# Bomba.net
KiCad netlist of a schematic drawn in EAGLE
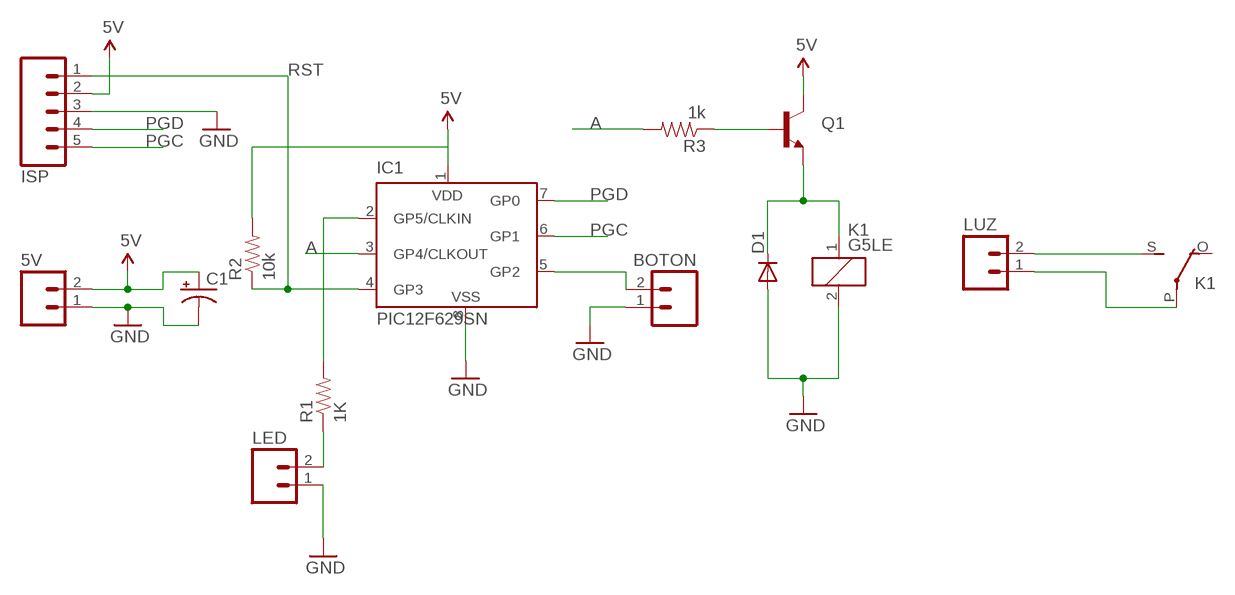
[diagram p0: schematic, sheet 1]

(export (version "E")
  (design (tool "Eeschema 10.0.6"))
  (components
    (comp (ref "5V")
      (value "M025MM")
      (footprint "eagle-import:SCREWTERMINAL-5MM-2")
      (libsource (lib "eagle-import") (part "M025MM"))
    )
    (comp (ref "BOTON")
      (value "M025MM")
      (footprint "eagle-import:SCREWTERMINAL-5MM-2")
      (libsource (lib "eagle-import") (part "M025MM"))
    )
    (comp (ref "C1")
      (value "CAP_POLPTH1")
      (footprint "eagle-import:CPOL-RADIAL-100UF-25V")
      (libsource (lib "eagle-import") (part "CAP_POLPTH1"))
    )
    (comp (ref "D1")
      (value "DIODE1N4148")
      (footprint "eagle-import:DIODE-1N4148")
      (libsource (lib "eagle-import") (part "DIODE1N4148"))
    )
    (comp (ref "IC1")
      (value "PIC12F629SN")
      (footprint "eagle-import:SO-08")
      (fields (field (name "MF") "MICROCHIP") (field (name "MPN") "PIC12F629-I/SN"))
      (libsource (lib "eagle-import") (part "PIC12F6SN29"))
    )
    (comp (ref "ISP")
      (value "M05LOCK_LONGPADS")
      (footprint "eagle-import:1X05_LOCK_LONGPADS")
      (libsource (lib "eagle-import") (part "M05LOCK_LONGPADS"))
    )
    (comp (ref "K1")
      (value "G5LE")
      (footprint "eagle-import:G5LE")
      (libsource (lib "eagle-import") (part "G5LE"))
    )
    (comp (ref "LED")
      (value "M02LOCK_LONGPADS")
      (footprint "eagle-import:1X02_LOCK_LONGPADS")
      (libsource (lib "eagle-import") (part "M02LOCK_LONGPADS"))
    )
    (comp (ref "LUZ")
      (value "M025MM")
      (footprint "eagle-import:SCREWTERMINAL-5MM-2")
      (libsource (lib "eagle-import") (part "M025MM"))
    )
    (comp (ref "Q1")
      (value "TRANSISTOR_NPNSOT23")
      (footprint "eagle-import:SOT23")
      (libsource (lib "eagle-import") (part "TRANSISTOR_NPNSOT23"))
    )
    (comp (ref "R1")
      (value "1K")
      (footprint "eagle-import:1206")
      (libsource (lib "eagle-import") (part "RESISTOR1206"))
    )
    (comp (ref "R2")
      (value "10k")
      (footprint "eagle-import:1206")
      (libsource (lib "eagle-import") (part "RESISTOR1206"))
    )
    (comp (ref "R3")
      (value "1k")
      (footprint "eagle-import:1206")
      (libsource (lib "eagle-import") (part "RESISTOR1206"))
    )
  )
  (nets
    (net (code "1") (name "/A") (class "Default")
      (node (ref "IC1") (pin "3") (pinfunction "GP4/CLKOUT_3") (pintype "bidirectional"))
      (node (ref "R3") (pin "2") (pinfunction "2_2") (pintype "passive"))
    )
    (net (code "2") (name "/PGC") (class "Default")
      (node (ref "IC1") (pin "6") (pinfunction "GP1_6") (pintype "bidirectional"))
      (node (ref "ISP") (pin "5") (pinfunction "5_5") (pintype "passive"))
    )
    (net (code "3") (name "/PGD") (class "Default")
      (node (ref "IC1") (pin "7") (pinfunction "GP0_7") (pintype "bidirectional"))
      (node (ref "ISP") (pin "4") (pinfunction "4_4") (pintype "passive"))
    )
    (net (code "4") (name "/RST") (class "Default")
      (node (ref "IC1") (pin "4") (pinfunction "GP3_4") (pintype "input"))
      (node (ref "ISP") (pin "1") (pinfunction "1_1") (pintype "passive"))
      (node (ref "R2") (pin "1") (pinfunction "1_1") (pintype "passive"))
    )
    (net (code "5") (name "5V") (class "Default")
      (node (ref "5V") (pin "2") (pinfunction "2_2") (pintype "passive"))
      (node (ref "C1") (pin "1") (pinfunction "+_1") (pintype "passive"))
      (node (ref "IC1") (pin "1") (pinfunction "VDD_1") (pintype "power_in"))
      (node (ref "ISP") (pin "2") (pinfunction "2_2") (pintype "passive"))
      (node (ref "Q1") (pin "3") (pinfunction "C_3") (pintype "passive"))
      (node (ref "R2") (pin "2") (pinfunction "2_2") (pintype "passive"))
    )
    (net (code "6") (name "GND") (class "Default")
      (node (ref "5V") (pin "1") (pinfunction "1_1") (pintype "passive"))
      (node (ref "BOTON") (pin "1") (pinfunction "1_1") (pintype "passive"))
      (node (ref "C1") (pin "2") (pinfunction "-_2") (pintype "passive"))
      (node (ref "D1") (pin "A") (pinfunction "A_A") (pintype "passive"))
      (node (ref "IC1") (pin "8") (pinfunction "VSS_8") (pintype "power_in"))
      (node (ref "ISP") (pin "3") (pinfunction "3_3") (pintype "passive"))
      (node (ref "K1") (pin "2") (pinfunction "2_2") (pintype "passive"))
      (node (ref "LED") (pin "1") (pinfunction "1_1") (pintype "passive"))
    )
    (net (code "7") (name "Net-(IC1-GP2)") (class "Default")
      (node (ref "BOTON") (pin "2") (pinfunction "2_2") (pintype "passive"))
      (node (ref "IC1") (pin "5") (pinfunction "GP2_5") (pintype "bidirectional"))
    )
    (net (code "8") (name "Net-(IC1-GP5{slash}CLKIN)") (class "Default")
      (node (ref "IC1") (pin "2") (pinfunction "GP5/CLKIN_2") (pintype "bidirectional"))
      (node (ref "R1") (pin "2") (pinfunction "2_2") (pintype "passive"))
    )
    (net (code "9") (name "Net-(K1-PadP)") (class "Default")
      (node (ref "K1") (pin "P") (pinfunction "P_P") (pintype "passive"))
      (node (ref "LUZ") (pin "1") (pinfunction "1_1") (pintype "passive"))
    )
    (net (code "10") (name "Net-(K1-PadS)") (class "Default")
      (node (ref "K1") (pin "S") (pinfunction "S_S") (pintype "passive"))
      (node (ref "LUZ") (pin "2") (pinfunction "2_2") (pintype "passive"))
    )
    (net (code "11") (name "Net-(LED-Pad2)") (class "Default")
      (node (ref "LED") (pin "2") (pinfunction "2_2") (pintype "passive"))
      (node (ref "R1") (pin "1") (pinfunction "1_1") (pintype "passive"))
    )
    (net (code "12") (name "Net-(Q1-B)") (class "Default")
      (node (ref "Q1") (pin "1") (pinfunction "B_1") (pintype "passive"))
      (node (ref "R3") (pin "1") (pinfunction "1_1") (pintype "passive"))
    )
    (net (code "13") (name "Net-(Q1-E)") (class "Default")
      (node (ref "D1") (pin "C") (pinfunction "C_C") (pintype "passive"))
      (node (ref "K1") (pin "1") (pinfunction "1_1") (pintype "passive"))
      (node (ref "Q1") (pin "2") (pinfunction "E_2") (pintype "passive"))
    )
    (net (code "14") (name "unconnected-(K1-PadO)") (class "Default")
      (node (ref "K1") (pin "O") (pinfunction "O_O") (pintype "passive"))
    )
  )
)
